# mm5823_2.net
KiCad netlist of a schematic drawn in EAGLE
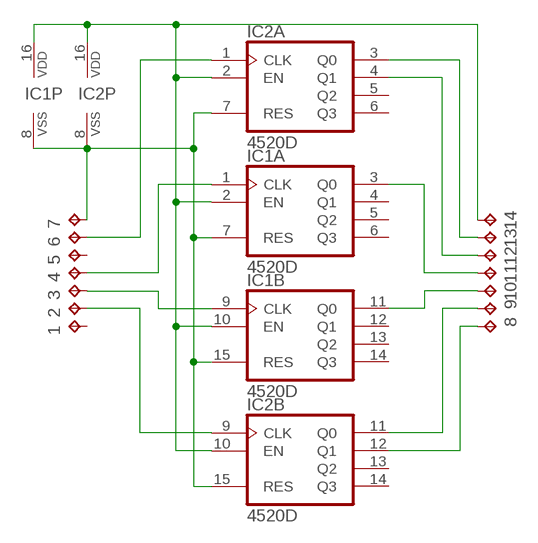
[diagram p0: schematic, sheet 1]

(export (version "E")
  (design (tool "Eeschema 10.0.6"))
  (components
    (comp (ref "1")
      (value "TPB1,27")
      (footprint "eagle-import:B1,27")
      (libsource (lib "eagle-import") (part "TPB1,27"))
    )
    (comp (ref "2")
      (value "TPB1,27")
      (footprint "eagle-import:B1,27")
      (libsource (lib "eagle-import") (part "TPB1,27"))
    )
    (comp (ref "3")
      (value "TPB1,27")
      (footprint "eagle-import:B1,27")
      (libsource (lib "eagle-import") (part "TPB1,27"))
    )
    (comp (ref "4")
      (value "TPB1,27")
      (footprint "eagle-import:B1,27")
      (libsource (lib "eagle-import") (part "TPB1,27"))
    )
    (comp (ref "5")
      (value "TPB1,27")
      (footprint "eagle-import:B1,27")
      (libsource (lib "eagle-import") (part "TPB1,27"))
    )
    (comp (ref "6")
      (value "TPB1,27")
      (footprint "eagle-import:B1,27")
      (libsource (lib "eagle-import") (part "TPB1,27"))
    )
    (comp (ref "7")
      (value "TPB1,27")
      (footprint "eagle-import:B1,27")
      (libsource (lib "eagle-import") (part "TPB1,27"))
    )
    (comp (ref "8")
      (value "TPB1,27")
      (footprint "eagle-import:B1,27")
      (libsource (lib "eagle-import") (part "TPB1,27"))
    )
    (comp (ref "9")
      (value "TPB1,27")
      (footprint "eagle-import:B1,27")
      (libsource (lib "eagle-import") (part "TPB1,27"))
    )
    (comp (ref "10")
      (value "TPB1,27")
      (footprint "eagle-import:B1,27")
      (libsource (lib "eagle-import") (part "TPB1,27"))
    )
    (comp (ref "11")
      (value "TPB1,27")
      (footprint "eagle-import:B1,27")
      (libsource (lib "eagle-import") (part "TPB1,27"))
    )
    (comp (ref "12")
      (value "TPB1,27")
      (footprint "eagle-import:B1,27")
      (libsource (lib "eagle-import") (part "TPB1,27"))
    )
    (comp (ref "13")
      (value "TPB1,27")
      (footprint "eagle-import:B1,27")
      (libsource (lib "eagle-import") (part "TPB1,27"))
    )
    (comp (ref "14")
      (value "TPB1,27")
      (footprint "eagle-import:B1,27")
      (libsource (lib "eagle-import") (part "TPB1,27"))
    )
    (comp (ref "IC1")
      (value "4520D")
      (footprint "eagle-import:SO16")
      (libsource (lib "eagle-import") (part "4520D"))
    )
    (comp (ref "IC2")
      (value "4520D")
      (footprint "eagle-import:SO16")
      (libsource (lib "eagle-import") (part "4520D"))
    )
  )
  (nets
    (net (code "1") (name "Net-(IC1A-CLK)") (class "Default")
      (node (ref "4") (pin "TP") (pinfunction "TP_TP") (pintype "input"))
      (node (ref "IC1") (pin "1") (pinfunction "CLK_1") (pintype "input"))
    )
    (net (code "2") (name "Net-(IC1A-EN)") (class "Default")
      (node (ref "14") (pin "TP") (pinfunction "TP_TP") (pintype "input"))
      (node (ref "IC1") (pin "10") (pinfunction "EN_10") (pintype "input"))
      (node (ref "IC1") (pin "16") (pinfunction "VDD_16") (pintype "power_in"))
      (node (ref "IC1") (pin "2") (pinfunction "EN_2") (pintype "input"))
      (node (ref "IC2") (pin "10") (pinfunction "EN_10") (pintype "input"))
      (node (ref "IC2") (pin "16") (pinfunction "VDD_16") (pintype "power_in"))
      (node (ref "IC2") (pin "2") (pinfunction "EN_2") (pintype "input"))
    )
    (net (code "3") (name "Net-(IC1A-Q0)") (class "Default")
      (node (ref "11") (pin "TP") (pinfunction "TP_TP") (pintype "input"))
      (node (ref "IC1") (pin "3") (pinfunction "Q0_3") (pintype "output"))
    )
    (net (code "4") (name "Net-(IC1A-RES)") (class "Default")
      (node (ref "7") (pin "TP") (pinfunction "TP_TP") (pintype "input"))
      (node (ref "IC1") (pin "15") (pinfunction "RES_15") (pintype "input"))
      (node (ref "IC1") (pin "7") (pinfunction "RES_7") (pintype "input"))
      (node (ref "IC1") (pin "8") (pinfunction "VSS_8") (pintype "power_in"))
      (node (ref "IC2") (pin "15") (pinfunction "RES_15") (pintype "input"))
      (node (ref "IC2") (pin "7") (pinfunction "RES_7") (pintype "input"))
      (node (ref "IC2") (pin "8") (pinfunction "VSS_8") (pintype "power_in"))
    )
    (net (code "5") (name "Net-(IC1B-CLK)") (class "Default")
      (node (ref "3") (pin "TP") (pinfunction "TP_TP") (pintype "input"))
      (node (ref "IC1") (pin "9") (pinfunction "CLK_9") (pintype "input"))
    )
    (net (code "6") (name "Net-(IC1B-Q0)") (class "Default")
      (node (ref "10") (pin "TP") (pinfunction "TP_TP") (pintype "input"))
      (node (ref "IC1") (pin "11") (pinfunction "Q0_11") (pintype "output"))
    )
    (net (code "7") (name "Net-(IC2A-CLK)") (class "Default")
      (node (ref "6") (pin "TP") (pinfunction "TP_TP") (pintype "input"))
      (node (ref "IC2") (pin "1") (pinfunction "CLK_1") (pintype "input"))
    )
    (net (code "8") (name "Net-(IC2A-Q0)") (class "Default")
      (node (ref "13") (pin "TP") (pinfunction "TP_TP") (pintype "input"))
      (node (ref "IC2") (pin "3") (pinfunction "Q0_3") (pintype "output"))
    )
    (net (code "9") (name "Net-(IC2A-Q1)") (class "Default")
      (node (ref "12") (pin "TP") (pinfunction "TP_TP") (pintype "input"))
      (node (ref "IC2") (pin "4") (pinfunction "Q1_4") (pintype "output"))
    )
    (net (code "10") (name "Net-(IC2B-CLK)") (class "Default")
      (node (ref "2") (pin "TP") (pinfunction "TP_TP") (pintype "input"))
      (node (ref "IC2") (pin "9") (pinfunction "CLK_9") (pintype "input"))
    )
    (net (code "11") (name "Net-(IC2B-Q0)") (class "Default")
      (node (ref "9") (pin "TP") (pinfunction "TP_TP") (pintype "input"))
      (node (ref "IC2") (pin "11") (pinfunction "Q0_11") (pintype "output"))
    )
    (net (code "12") (name "Net-(IC2B-Q1)") (class "Default")
      (node (ref "8") (pin "TP") (pinfunction "TP_TP") (pintype "input"))
      (node (ref "IC2") (pin "12") (pinfunction "Q1_12") (pintype "output"))
    )
    (net (code "13") (name "unconnected-(1-PadTP)") (class "Default")
      (node (ref "1") (pin "TP") (pinfunction "TP_TP") (pintype "input"))
    )
    (net (code "14") (name "unconnected-(5-PadTP)") (class "Default")
      (node (ref "5") (pin "TP") (pinfunction "TP_TP") (pintype "input"))
    )
    (net (code "15") (name "unconnected-(IC1A-Q1-Pad4)") (class "Default")
      (node (ref "IC1") (pin "4") (pinfunction "Q1_4") (pintype "output"))
    )
    (net (code "16") (name "unconnected-(IC1A-Q2-Pad5)") (class "Default")
      (node (ref "IC1") (pin "5") (pinfunction "Q2_5") (pintype "output"))
    )
    (net (code "17") (name "unconnected-(IC1A-Q3-Pad6)") (class "Default")
      (node (ref "IC1") (pin "6") (pinfunction "Q3_6") (pintype "output"))
    )
    (net (code "18") (name "unconnected-(IC1B-Q1-Pad12)") (class "Default")
      (node (ref "IC1") (pin "12") (pinfunction "Q1_12") (pintype "output"))
    )
    (net (code "19") (name "unconnected-(IC1B-Q2-Pad13)") (class "Default")
      (node (ref "IC1") (pin "13") (pinfunction "Q2_13") (pintype "output"))
    )
    (net (code "20") (name "unconnected-(IC1B-Q3-Pad14)") (class "Default")
      (node (ref "IC1") (pin "14") (pinfunction "Q3_14") (pintype "output"))
    )
    (net (code "21") (name "unconnected-(IC2A-Q2-Pad5)") (class "Default")
      (node (ref "IC2") (pin "5") (pinfunction "Q2_5") (pintype "output"))
    )
    (net (code "22") (name "unconnected-(IC2A-Q3-Pad6)") (class "Default")
      (node (ref "IC2") (pin "6") (pinfunction "Q3_6") (pintype "output"))
    )
    (net (code "23") (name "unconnected-(IC2B-Q2-Pad13)") (class "Default")
      (node (ref "IC2") (pin "13") (pinfunction "Q2_13") (pintype "output"))
    )
    (net (code "24") (name "unconnected-(IC2B-Q3-Pad14)") (class "Default")
      (node (ref "IC2") (pin "14") (pinfunction "Q3_14") (pintype "output"))
    )
  )
)
